# Schematic_v1.net
KiCad netlist of a schematic drawn in Altium Designer
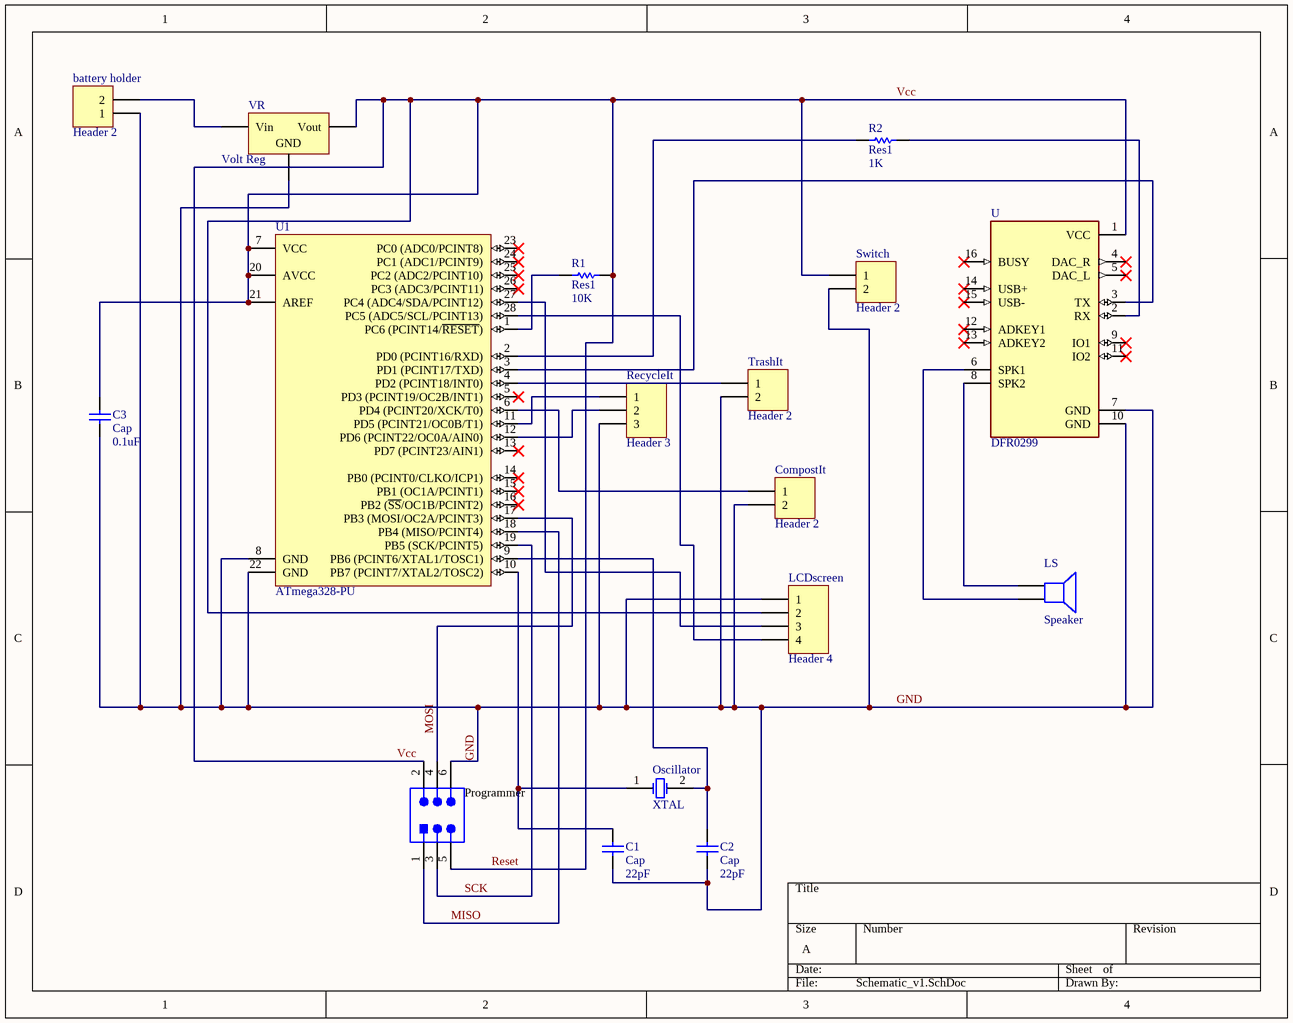
[diagram p0: Schematic_v1.SchDoc]

(export (version "E")
  (design (tool "Eeschema 10.0.6"))
  (components
    (comp (ref "battery holder")
      (value "Header 2")
      (footprint "HDR1X2")
      (description "Header, 2-Pin")
      (fields (field (name "PUBLISHER") "Altium Limited"))
      (libsource (lib "") (part "Header 2_1"))
    )
    (comp (ref "C1")
      (value "Cap")
      (footprint "RAD-0.3")
      (description "Capacitor")
      (fields (field (name "ALTIUM_VALUE") "22pF") (field (name "PUBLISHER") "Altium Limited"))
      (libsource (lib "Miscellaneous Devices") (part "Cap"))
    )
    (comp (ref "C2")
      (value "Cap")
      (footprint "RAD-0.3")
      (description "Capacitor")
      (fields (field (name "ALTIUM_VALUE") "22pF") (field (name "PUBLISHER") "Altium Limited"))
      (libsource (lib "Miscellaneous Devices") (part "Cap"))
    )
    (comp (ref "C3")
      (value "Cap")
      (footprint "RAD-0.3")
      (description "Capacitor")
      (fields (field (name "ALTIUM_VALUE") "0.1uF") (field (name "PUBLISHER") "Altium Limited"))
      (libsource (lib "Miscellaneous Devices") (part "Cap"))
    )
    (comp (ref "CompostIt")
      (value "Header 2")
      (footprint "HDR1X2")
      (description "Header, 2-Pin")
      (fields (field (name "PUBLISHER") "Altium Limited"))
      (libsource (lib "Miscellaneous Connectors") (part "Header 2"))
    )
    (comp (ref "LCDscreen")
      (value "Header 4")
      (footprint "HDR1X4")
      (description "Header, 4-Pin")
      (fields (field (name "PUBLISHER") "Altium Limited"))
      (libsource (lib "Miscellaneous Connectors") (part "Header 4"))
    )
    (comp (ref "LS")
      (value "Speaker")
      (footprint "PIN2")
      (description "Loudspeaker")
      (fields (field (name "PUBLISHER") "Altium Limited"))
      (libsource (lib "Miscellaneous Devices") (part "Speaker"))
    )
    (comp (ref "Oscillator")
      (value "XTAL")
      (footprint "R38")
      (description "Crystal Oscillator")
      (fields (field (name "PUBLISHER") "Altium Limited"))
      (libsource (lib "Miscellaneous Devices") (part "XTAL"))
    )
    (comp (ref "Programmer")
      (value "TSW-103-08-L-D")
      (footprint "SMTC-TSW-103-08-L-D_V")
      (fields (field (name "MANUFACTURER") "Samtec"))
      (libsource (lib "Altium Content Vault") (part "CN-2P-M-R6"))
    )
    (comp (ref "R1")
      (value "Res1")
      (footprint "AXIAL-0.3")
      (description "Resistor")
      (fields (field (name "ALTIUM_VALUE") "10K") (field (name "PUBLISHER") "Altium Limited"))
      (libsource (lib "Miscellaneous Devices") (part "Res1"))
    )
    (comp (ref "R2")
      (value "Res1")
      (footprint "AXIAL-0.3")
      (description "Resistor")
      (fields (field (name "ALTIUM_VALUE") "1K") (field (name "PUBLISHER") "Altium Limited"))
      (libsource (lib "Miscellaneous Devices") (part "Res1"))
    )
    (comp (ref "RecycleIt")
      (value "Header 3")
      (footprint "HDR1X3")
      (description "Header, 3-Pin")
      (fields (field (name "PUBLISHER") "Altium Limited"))
      (libsource (lib "Miscellaneous Connectors") (part "Header 3"))
    )
    (comp (ref "Switch")
      (value "Header 2")
      (footprint "HDR1X2")
      (description "Header, 2-Pin")
      (fields (field (name "PUBLISHER") "Altium Limited"))
      (libsource (lib "Miscellaneous Connectors") (part "Header 2"))
    )
    (comp (ref "TrashIt")
      (value "Header 2")
      (footprint "HDR1X2")
      (description "Header, 2-Pin")
      (fields (field (name "PUBLISHER") "Altium Limited"))
      (libsource (lib "Miscellaneous Connectors") (part "Header 2"))
    )
    (comp (ref "U")
      (value "DFR0299")
      (footprint "MODULE_DFR0299")
      (description "MP3 Player Audio Arduino Platform Evaluation Expansion Board")
      (fields (field (name "MF") "DFRobot"))
      (libsource (lib "DFR0299") (part "DFR0299"))
    )
    (comp (ref "U1")
      (value "ATmega328-PU")
      (footprint "28P3")
      (libsource (lib "Altium Content Vault") (part "MC-8B-ATM48-IL28"))
    )
    (comp (ref "VR")
      (value "Volt Reg")
      (footprint "D2PAK_N")
      (description "Voltage Regulator")
      (fields (field (name "PUBLISHER") "Altium Limited"))
      (libsource (lib "Miscellaneous Devices") (part "Volt Reg"))
    )
  )
  (nets
    (net (code "1") (name "/GND") (class "Default")
      (node (ref "C1") (pin "1") (pinfunction "1_1") (pintype "passive"))
      (node (ref "C2") (pin "1") (pinfunction "1_1") (pintype "passive"))
      (node (ref "C3") (pin "1") (pinfunction "1_1") (pintype "passive"))
      (node (ref "CompostIt") (pin "2") (pinfunction "2_2") (pintype "passive"))
      (node (ref "LCDscreen") (pin "1") (pinfunction "1_1") (pintype "passive"))
      (node (ref "Programmer") (pin "6") (pinfunction "6_6") (pintype "passive"))
      (node (ref "RecycleIt") (pin "3") (pinfunction "3_3") (pintype "passive"))
      (node (ref "Switch") (pin "2") (pinfunction "2_2") (pintype "passive"))
      (node (ref "TrashIt") (pin "2") (pinfunction "2_2") (pintype "passive"))
      (node (ref "U") (pin "10") (pinfunction "GND_10") (pintype "power_in"))
      (node (ref "U") (pin "7") (pinfunction "GND_7") (pintype "power_in"))
      (node (ref "U1") (pin "22") (pinfunction "GND_22") (pintype "power_in"))
      (node (ref "U1") (pin "8") (pinfunction "GND_8") (pintype "power_in"))
      (node (ref "VR") (pin "2") (pinfunction "GND_2") (pintype "passive"))
      (node (ref "battery holder") (pin "1") (pinfunction "1_1") (pintype "passive"))
    )
    (net (code "2") (name "/MISO") (class "Default")
      (node (ref "Programmer") (pin "1") (pinfunction "1_1") (pintype "passive"))
      (node (ref "U1") (pin "18") (pinfunction "PB4_(MISO/PCINT4)_18") (pintype "bidirectional"))
    )
    (net (code "3") (name "/MOSI") (class "Default")
      (node (ref "Programmer") (pin "4") (pinfunction "4_4") (pintype "passive"))
      (node (ref "U1") (pin "17") (pinfunction "PB3_(MOSI/OC2A/PCINT3)_17") (pintype "bidirectional"))
    )
    (net (code "4") (name "/Reset") (class "Default")
      (node (ref "C3") (pin "2") (pinfunction "2_2") (pintype "passive"))
      (node (ref "LCDscreen") (pin "2") (pinfunction "2_2") (pintype "passive"))
      (node (ref "Programmer") (pin "2") (pinfunction "2_2") (pintype "passive"))
      (node (ref "Programmer") (pin "5") (pinfunction "5_5") (pintype "passive"))
      (node (ref "R1") (pin "2") (pinfunction "2_2") (pintype "passive"))
      (node (ref "Switch") (pin "1") (pinfunction "1_1") (pintype "passive"))
      (node (ref "U") (pin "1") (pinfunction "VCC_1") (pintype "power_in"))
      (node (ref "U1") (pin "20") (pinfunction "AVCC_20") (pintype "power_in"))
      (node (ref "U1") (pin "21") (pinfunction "AREF_21") (pintype "power_in"))
      (node (ref "U1") (pin "7") (pinfunction "VCC_7") (pintype "power_in"))
      (node (ref "VR") (pin "3") (pinfunction "Vout_3") (pintype "passive"))
    )
    (net (code "5") (name "/SCK") (class "Default")
      (node (ref "Programmer") (pin "3") (pinfunction "3_3") (pintype "passive"))
      (node (ref "U1") (pin "19") (pinfunction "PB5_(SCK/PCINT5)_19") (pintype "bidirectional"))
    )
    (net (code "6") (name "Net-(Oscillator-OSC1)") (class "Default")
      (node (ref "C1") (pin "2") (pinfunction "2_2") (pintype "passive"))
      (node (ref "Oscillator") (pin "1") (pinfunction "OSC1_1") (pintype "passive"))
      (node (ref "U1") (pin "10") (pinfunction "PB7_(PCINT7/XTAL2/TOSC2)_10") (pintype "bidirectional"))
    )
    (net (code "7") (name "Net-(Oscillator-OSC2)") (class "Default")
      (node (ref "C2") (pin "2") (pinfunction "2_2") (pintype "passive"))
      (node (ref "Oscillator") (pin "2") (pinfunction "OSC2_2") (pintype "passive"))
      (node (ref "U1") (pin "9") (pinfunction "PB6_(PCINT6/XTAL1/TOSC1)_9") (pintype "bidirectional"))
    )
    (net (code "8") (name "Net-(U-RX)") (class "Default")
      (node (ref "R2") (pin "2") (pinfunction "2_2") (pintype "passive"))
      (node (ref "U") (pin "2") (pinfunction "RX_2") (pintype "bidirectional"))
    )
    (net (code "9") (name "Net-(U-SPK1)") (class "Default")
      (node (ref "LS") (pin "2") (pinfunction "2_2") (pintype "passive"))
      (node (ref "U") (pin "6") (pinfunction "SPK1_6") (pintype "passive"))
    )
    (net (code "10") (name "Net-(U-SPK2)") (class "Default")
      (node (ref "LS") (pin "1") (pinfunction "1_1") (pintype "passive"))
      (node (ref "U") (pin "8") (pinfunction "SPK2_8") (pintype "passive"))
    )
    (net (code "11") (name "Net-(U-TX)") (class "Default")
      (node (ref "U") (pin "3") (pinfunction "TX_3") (pintype "bidirectional"))
      (node (ref "U1") (pin "3") (pinfunction "PD1_(PCINT17/TXD)_3") (pintype "bidirectional"))
    )
    (net (code "12") (name "Net-(U1-PC4_(ADC4{slash}SDA{slash}PCINT12))") (class "Default")
      (node (ref "LCDscreen") (pin "3") (pinfunction "3_3") (pintype "passive"))
      (node (ref "U1") (pin "27") (pinfunction "PC4_(ADC4/SDA/PCINT12)_27") (pintype "bidirectional"))
    )
    (net (code "13") (name "Net-(U1-PC5_(ADC5{slash}SCL{slash}PCINT13))") (class "Default")
      (node (ref "LCDscreen") (pin "4") (pinfunction "4_4") (pintype "passive"))
      (node (ref "U1") (pin "28") (pinfunction "PC5_(ADC5/SCL/PCINT13)_28") (pintype "bidirectional"))
    )
    (net (code "14") (name "Net-(U1-PC6_(PCINT14{slash}~{RESET}))") (class "Default")
      (node (ref "R1") (pin "1") (pinfunction "1_1") (pintype "passive"))
      (node (ref "U1") (pin "1") (pinfunction "PC6_(PCINT14/~{RESET})_1") (pintype "bidirectional"))
    )
    (net (code "15") (name "Net-(U1-PD0_(PCINT16{slash}RXD))") (class "Default")
      (node (ref "R2") (pin "1") (pinfunction "1_1") (pintype "passive"))
      (node (ref "U1") (pin "2") (pinfunction "PD0_(PCINT16/RXD)_2") (pintype "bidirectional"))
    )
    (net (code "16") (name "Net-(U1-PD2_(PCINT18{slash}INT0))") (class "Default")
      (node (ref "TrashIt") (pin "1") (pinfunction "1_1") (pintype "passive"))
      (node (ref "U1") (pin "4") (pinfunction "PD2_(PCINT18/INT0)_4") (pintype "bidirectional"))
    )
    (net (code "17") (name "Net-(U1-PD4_(PCINT20{slash}XCK{slash}T0))") (class "Default")
      (node (ref "CompostIt") (pin "1") (pinfunction "1_1") (pintype "passive"))
      (node (ref "U1") (pin "6") (pinfunction "PD4_(PCINT20/XCK/T0)_6") (pintype "bidirectional"))
    )
    (net (code "18") (name "Net-(U1-PD5_(PCINT21{slash}OC0B{slash}T1))") (class "Default")
      (node (ref "RecycleIt") (pin "1") (pinfunction "1_1") (pintype "passive"))
      (node (ref "U1") (pin "11") (pinfunction "PD5_(PCINT21/OC0B/T1)_11") (pintype "bidirectional"))
    )
    (net (code "19") (name "Net-(U1-PD6_(PCINT22{slash}OC0A{slash}AIN0))") (class "Default")
      (node (ref "RecycleIt") (pin "2") (pinfunction "2_2") (pintype "passive"))
      (node (ref "U1") (pin "12") (pinfunction "PD6_(PCINT22/OC0A/AIN0)_12") (pintype "bidirectional"))
    )
    (net (code "20") (name "Net-(VR-Vin)") (class "Default")
      (node (ref "VR") (pin "1") (pinfunction "Vin_1") (pintype "passive"))
      (node (ref "battery holder") (pin "2") (pinfunction "2_2") (pintype "passive"))
    )
    (net (code "21") (name "unconnected-(U-ADKEY1-Pad12)") (class "Default")
      (node (ref "U") (pin "12") (pinfunction "ADKEY1_12") (pintype "input+no_connect"))
    )
    (net (code "22") (name "unconnected-(U-ADKEY2-Pad13)") (class "Default")
      (node (ref "U") (pin "13") (pinfunction "ADKEY2_13") (pintype "input+no_connect"))
    )
    (net (code "23") (name "unconnected-(U-BUSY-Pad16)") (class "Default")
      (node (ref "U") (pin "16") (pinfunction "BUSY_16") (pintype "input+no_connect"))
    )
    (net (code "24") (name "unconnected-(U-DAC_L-Pad5)") (class "Default")
      (node (ref "U") (pin "5") (pinfunction "DAC_L_5") (pintype "output+no_connect"))
    )
    (net (code "25") (name "unconnected-(U-DAC_R-Pad4)") (class "Default")
      (node (ref "U") (pin "4") (pinfunction "DAC_R_4") (pintype "output+no_connect"))
    )
    (net (code "26") (name "unconnected-(U-IO1-Pad9)") (class "Default")
      (node (ref "U") (pin "9") (pinfunction "IO1_9") (pintype "bidirectional+no_connect"))
    )
    (net (code "27") (name "unconnected-(U-IO2-Pad11)") (class "Default")
      (node (ref "U") (pin "11") (pinfunction "IO2_11") (pintype "bidirectional+no_connect"))
    )
    (net (code "28") (name "unconnected-(U-USB+-Pad14)") (class "Default")
      (node (ref "U") (pin "14") (pinfunction "USB+_14") (pintype "input+no_connect"))
    )
    (net (code "29") (name "unconnected-(U-USB--Pad15)") (class "Default")
      (node (ref "U") (pin "15") (pinfunction "USB-_15") (pintype "input+no_connect"))
    )
    (net (code "30") (name "unconnected-(U1-PB0_(PCINT0{slash}CLKO{slash}ICP1)-Pad14)") (class "Default")
      (node (ref "U1") (pin "14") (pinfunction "PB0_(PCINT0/CLKO/ICP1)_14") (pintype "bidirectional+no_connect"))
    )
    (net (code "31") (name "unconnected-(U1-PB1_(OC1A{slash}PCINT1)-Pad15)") (class "Default")
      (node (ref "U1") (pin "15") (pinfunction "PB1_(OC1A/PCINT1)_15") (pintype "bidirectional+no_connect"))
    )
    (net (code "32") (name "unconnected-(U1-PB2_(~{SS}{slash}OC1B{slash}PCINT2)-Pad16)") (class "Default")
      (node (ref "U1") (pin "16") (pinfunction "PB2_(~{SS}/OC1B/PCINT2)_16") (pintype "bidirectional+no_connect"))
    )
    (net (code "33") (name "unconnected-(U1-PC0_(ADC0{slash}PCINT8)-Pad23)") (class "Default")
      (node (ref "U1") (pin "23") (pinfunction "PC0_(ADC0/PCINT8)_23") (pintype "bidirectional+no_connect"))
    )
    (net (code "34") (name "unconnected-(U1-PC1_(ADC1{slash}PCINT9)-Pad24)") (class "Default")
      (node (ref "U1") (pin "24") (pinfunction "PC1_(ADC1/PCINT9)_24") (pintype "bidirectional+no_connect"))
    )
    (net (code "35") (name "unconnected-(U1-PC2_(ADC2{slash}PCINT10)-Pad25)") (class "Default")
      (node (ref "U1") (pin "25") (pinfunction "PC2_(ADC2/PCINT10)_25") (pintype "bidirectional+no_connect"))
    )
    (net (code "36") (name "unconnected-(U1-PC3_(ADC3{slash}PCINT11)-Pad26)") (class "Default")
      (node (ref "U1") (pin "26") (pinfunction "PC3_(ADC3/PCINT11)_26") (pintype "bidirectional+no_connect"))
    )
    (net (code "37") (name "unconnected-(U1-PD3_(PCINT19{slash}OC2B{slash}INT1)-Pad5)") (class "Default")
      (node (ref "U1") (pin "5") (pinfunction "PD3_(PCINT19/OC2B/INT1)_5") (pintype "bidirectional+no_connect"))
    )
    (net (code "38") (name "unconnected-(U1-PD7_(PCINT23{slash}AIN1)-Pad13)") (class "Default")
      (node (ref "U1") (pin "13") (pinfunction "PD7_(PCINT23/AIN1)_13") (pintype "bidirectional+no_connect"))
    )
  )
)
